# Inp.net
KiCad netlist of a schematic drawn in Altium Designer
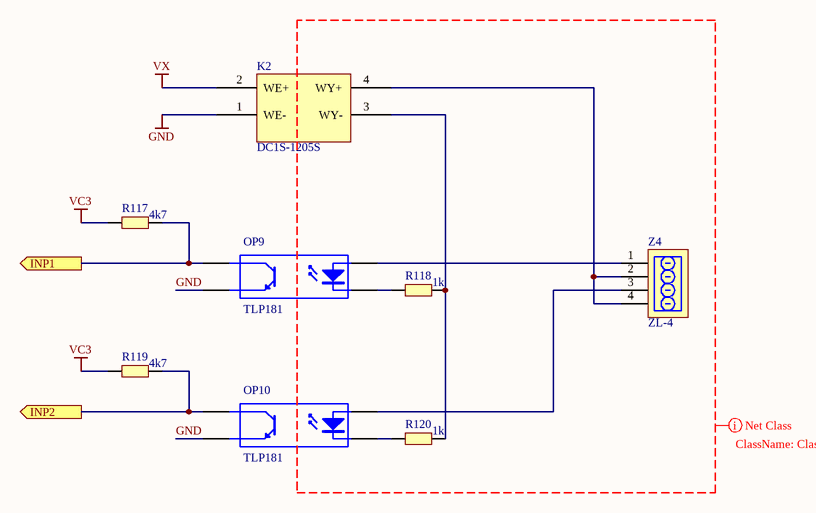
[diagram p0: Inp.SchDoc]

(export (version "E")
  (design (tool "Eeschema 10.0.6"))
  (components
    (comp (ref "K2")
      (value "DC1S-1205S")
      (footprint "DCDC_SIL4")
      (libsource (lib "ElhosSchLib") (part "DCDC_AM1S"))
    )
    (comp (ref "OP9")
      (value "TLP181")
      (footprint "TLP181_1")
      (description "Optoisolator")
      (libsource (lib "*") (part "TLP621"))
    )
    (comp (ref "OP10")
      (value "TLP181")
      (footprint "TLP181_1")
      (description "Optoisolator")
      (libsource (lib "*") (part "TLP621"))
    )
    (comp (ref "R117") (value "4k7") (footprint "0603R") (libsource (lib "*") (part "RES3")))
    (comp (ref "R118") (value "1k") (footprint "0805R") (libsource (lib "*") (part "RES3")))
    (comp (ref "R119") (value "4k7") (footprint "0603R") (libsource (lib "*") (part "RES3")))
    (comp (ref "R120") (value "1k") (footprint "0805R") (libsource (lib "*") (part "RES3")))
    (comp (ref "Z4") (value "ZL-4") (footprint "ARC-4-3.5-TYCO-1") (libsource (lib "*") (part "ZL-4")))
  )
  (nets
    (net (code "1") (name "/INP1") (class "Default")
      (node (ref "OP9") (pin "4") (pinfunction "3_4") (pintype "passive"))
      (node (ref "R117") (pin "1") (pintype "passive"))
    )
    (net (code "2") (name "/INP2") (class "Default")
      (node (ref "OP10") (pin "4") (pinfunction "3_4") (pintype "passive"))
      (node (ref "R119") (pin "1") (pintype "passive"))
    )
    (net (code "3") (name "GND") (class "Default")
      (node (ref "K2") (pin "1") (pinfunction "WE-_1") (pintype "passive"))
      (node (ref "OP10") (pin "3") (pinfunction "4_3") (pintype "passive"))
      (node (ref "OP9") (pin "3") (pinfunction "4_3") (pintype "passive"))
    )
    (net (code "4") (name "Net-(K2-WY+)") (class "Default")
      (node (ref "K2") (pin "4") (pinfunction "WY+_4") (pintype "passive"))
      (node (ref "Z4") (pin "2") (pintype "passive"))
      (node (ref "Z4") (pin "4") (pintype "passive"))
    )
    (net (code "5") (name "Net-(K2-WY-)") (class "Default")
      (node (ref "K2") (pin "3") (pinfunction "WY-_3") (pintype "passive"))
      (node (ref "R118") (pin "1") (pintype "passive"))
      (node (ref "R120") (pin "1") (pintype "passive"))
    )
    (net (code "6") (name "Net-(OP9-Pad1)") (class "Default")
      (node (ref "OP9") (pin "1") (pinfunction "1_1") (pintype "passive"))
      (node (ref "Z4") (pin "1") (pintype "passive"))
    )
    (net (code "7") (name "Net-(OP9-Pad2)") (class "Default")
      (node (ref "OP9") (pin "2") (pinfunction "2_2") (pintype "passive"))
      (node (ref "R118") (pin "2") (pintype "passive"))
    )
    (net (code "8") (name "Net-(OP10-Pad1)") (class "Default")
      (node (ref "OP10") (pin "1") (pinfunction "1_1") (pintype "passive"))
      (node (ref "Z4") (pin "3") (pintype "passive"))
    )
    (net (code "9") (name "Net-(OP10-Pad2)") (class "Default")
      (node (ref "OP10") (pin "2") (pinfunction "2_2") (pintype "passive"))
      (node (ref "R120") (pin "2") (pintype "passive"))
    )
    (net (code "10") (name "VC3") (class "Default")
      (node (ref "R117") (pin "2") (pintype "passive"))
      (node (ref "R119") (pin "2") (pintype "passive"))
    )
    (net (code "11") (name "VX") (class "Default")
      (node (ref "K2") (pin "2") (pinfunction "WE+_2") (pintype "passive"))
    )
  )
)
